# GWLSensorv6.net
KiCad netlist of a schematic drawn in EAGLE
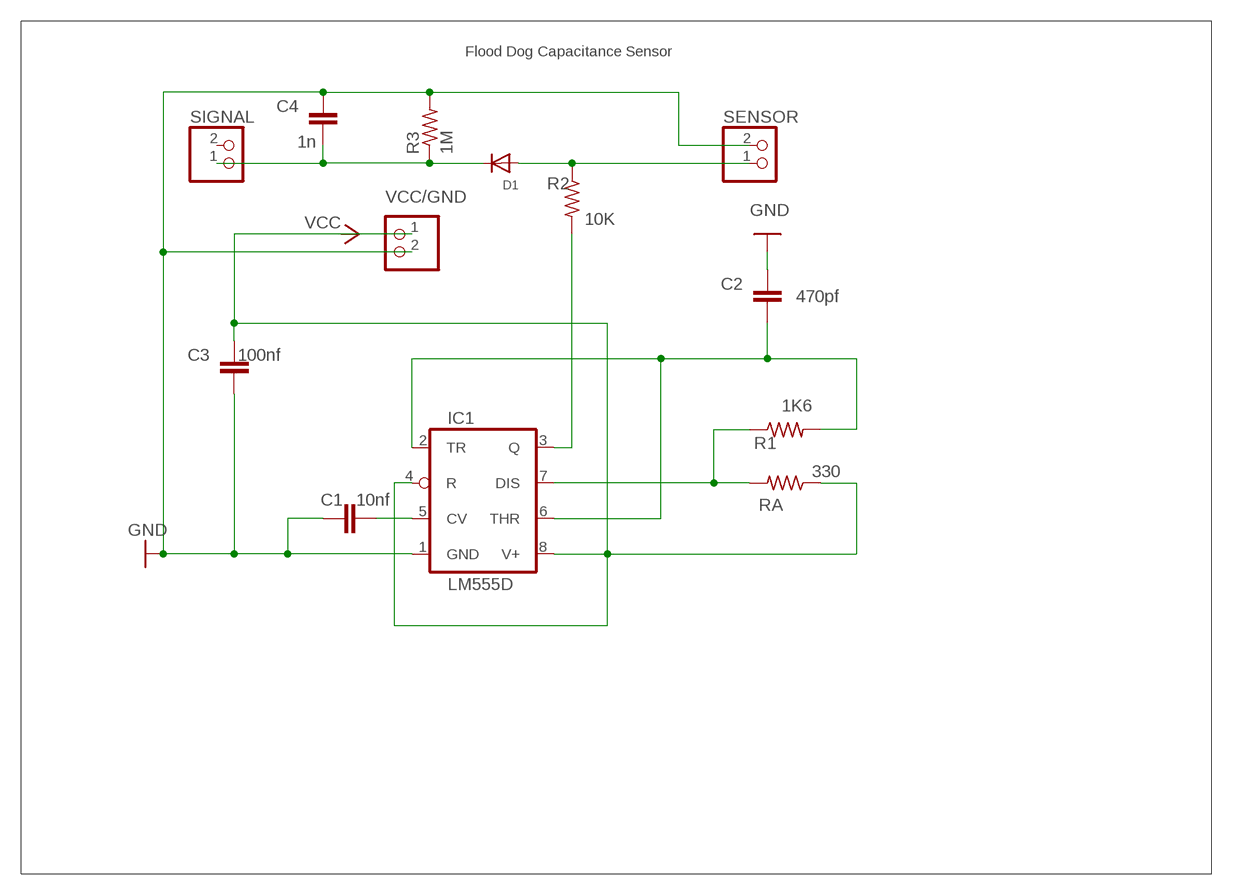
[diagram p0: schematic, sheet 1]

(export (version "E")
  (design (tool "Eeschema 10.0.6"))
  (components
    (comp (ref "C1")
      (value "10nf")
      (footprint "eagle-import:C0805")
      (libsource (lib "eagle-import") (part "C-EUC0805"))
    )
    (comp (ref "C2")
      (value "470pf")
      (footprint "eagle-import:C0805")
      (libsource (lib "eagle-import") (part "C-EUC0805"))
    )
    (comp (ref "C3")
      (value "100nf")
      (footprint "eagle-import:C0805")
      (libsource (lib "eagle-import") (part "C-EUC0805"))
    )
    (comp (ref "C4")
      (value "1n")
      (footprint "eagle-import:C0805")
      (libsource (lib "eagle-import") (part "C-EUC0805"))
    )
    (comp (ref "D1")
      (value "DIODESMA")
      (footprint "eagle-import:SMADIODE")
      (libsource (lib "eagle-import") (part "DIODESMA"))
    )
    (comp (ref "IC1")
      (value "LM555D")
      (footprint "eagle-import:SO08")
      (libsource (lib "eagle-import") (part "555DLM"))
    )
    (comp (ref "R1")
      (value "1K6")
      (footprint "eagle-import:R0805")
      (libsource (lib "eagle-import") (part "R-US_R0805"))
    )
    (comp (ref "R2")
      (value "10K")
      (footprint "eagle-import:R0805")
      (libsource (lib "eagle-import") (part "R-US_R0805"))
    )
    (comp (ref "R3")
      (value "1M")
      (footprint "eagle-import:R0805")
      (libsource (lib "eagle-import") (part "R-US_R0805"))
    )
    (comp (ref "RA")
      (value "330")
      (footprint "eagle-import:R0805")
      (libsource (lib "eagle-import") (part "R-US_R0805"))
    )
    (comp (ref "SENSOR")
      (value "JST_2PIN-SMT")
      (footprint "eagle-import:JST-PH-2-SMT")
      (libsource (lib "eagle-import") (part "JST_2PIN-SMT"))
    )
    (comp (ref "SIGNAL")
      (value "JST_2PIN-SMT")
      (footprint "eagle-import:JST-PH-2-SMT")
      (libsource (lib "eagle-import") (part "JST_2PIN-SMT"))
    )
    (comp (ref "VCC/GND")
      (value "JST_2PIN-SMT")
      (footprint "eagle-import:JST-PH-2-SMT")
      (libsource (lib "eagle-import") (part "JST_2PIN-SMT"))
    )
  )
  (nets
    (net (code "1") (name "GND") (class "Default")
      (node (ref "C1") (pin "1") (pinfunction "1_1") (pintype "passive"))
      (node (ref "C2") (pin "2") (pinfunction "2_2") (pintype "passive"))
      (node (ref "C3") (pin "1") (pinfunction "1_1") (pintype "passive"))
      (node (ref "C4") (pin "2") (pinfunction "2_2") (pintype "passive"))
      (node (ref "IC1") (pin "1") (pinfunction "GND_1") (pintype "power_in"))
      (node (ref "R3") (pin "2") (pinfunction "2_2") (pintype "passive"))
      (node (ref "SENSOR") (pin "2") (pinfunction "1_2") (pintype "passive"))
      (node (ref "VCC/GND") (pin "2") (pinfunction "1_2") (pintype "passive"))
    )
    (net (code "2") (name "Net-(IC1-CV)") (class "Default")
      (node (ref "C1") (pin "2") (pinfunction "2_2") (pintype "passive"))
      (node (ref "IC1") (pin "5") (pinfunction "CV_5") (pintype "input"))
    )
    (net (code "3") (name "Net-(IC1-DIS)") (class "Default")
      (node (ref "IC1") (pin "7") (pinfunction "DIS_7") (pintype "input"))
      (node (ref "R1") (pin "1") (pinfunction "1_1") (pintype "passive"))
      (node (ref "RA") (pin "2") (pinfunction "2_2") (pintype "passive"))
    )
    (net (code "4") (name "Net-(IC1-Q)") (class "Default")
      (node (ref "IC1") (pin "3") (pinfunction "Q_3") (pintype "output"))
      (node (ref "R2") (pin "2") (pinfunction "2_2") (pintype "passive"))
    )
    (net (code "5") (name "Net-(IC1-THR)") (class "Default")
      (node (ref "C2") (pin "1") (pinfunction "1_1") (pintype "passive"))
      (node (ref "IC1") (pin "2") (pinfunction "TR_2") (pintype "input"))
      (node (ref "IC1") (pin "6") (pinfunction "THR_6") (pintype "input"))
      (node (ref "R1") (pin "2") (pinfunction "2_2") (pintype "passive"))
    )
    (net (code "6") (name "Net-(SENSOR-2)") (class "Default")
      (node (ref "D1") (pin "A") (pinfunction "A_A") (pintype "passive"))
      (node (ref "R2") (pin "1") (pinfunction "1_1") (pintype "passive"))
      (node (ref "SENSOR") (pin "1") (pinfunction "2_1") (pintype "passive"))
    )
    (net (code "7") (name "Net-(SIGNAL-2)") (class "Default")
      (node (ref "C4") (pin "1") (pinfunction "1_1") (pintype "passive"))
      (node (ref "D1") (pin "C") (pinfunction "C_C") (pintype "passive"))
      (node (ref "R3") (pin "1") (pinfunction "1_1") (pintype "passive"))
      (node (ref "SIGNAL") (pin "1") (pinfunction "2_1") (pintype "passive"))
    )
    (net (code "8") (name "VCC") (class "Default")
      (node (ref "C3") (pin "2") (pinfunction "2_2") (pintype "passive"))
      (node (ref "IC1") (pin "4") (pinfunction "R_4") (pintype "input"))
      (node (ref "IC1") (pin "8") (pinfunction "V+_8") (pintype "power_in"))
      (node (ref "RA") (pin "1") (pinfunction "1_1") (pintype "passive"))
      (node (ref "VCC/GND") (pin "1") (pinfunction "2_1") (pintype "passive"))
    )
    (net (code "9") (name "unconnected-(SIGNAL-1-Pad2)") (class "Default")
      (node (ref "SIGNAL") (pin "2") (pinfunction "1_2") (pintype "passive"))
    )
  )
)
